# Flash_RAM.net
KiCad netlist of a schematic drawn in Altium Designer
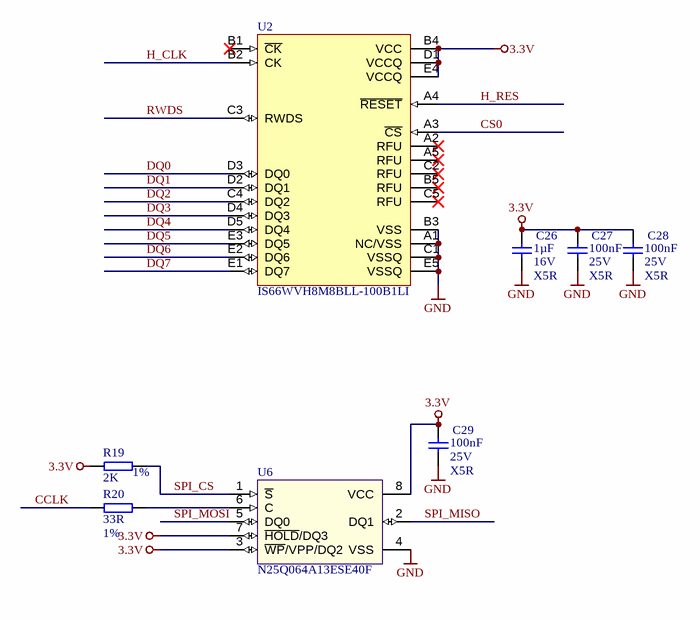
[diagram p0: Flash_RAM.SchDoc]

(export (version "E")
  (design (tool "Eeschema 10.0.6"))
  (components
    (comp (ref "C26")
      (value "1µF")
      (footprint "CAPC1005X55N")
      (description "KON 1µF 16V X5R 10% SMD BF 1005 (0402)")
      (fields
        (field (name "VOLTAGE") "16V")
        (field (name "TECHNOLOGY") "X5R")
        (field (name "TOLERANCE") "10%")
      )
      (libsource (lib "TE") (part "CAP-NP"))
    )
    (comp (ref "C27")
      (value "100nF")
      (footprint "CAPC1005X55N")
      (description "KON 100nF 25V X5R ±10% SMD BF 1005 (0402)")
      (fields (field (name "VOLTAGE") "25V") (field (name "TECHNOLOGY") "X5R"))
      (libsource (lib "TE") (part "CAP-NP"))
    )
    (comp (ref "C28")
      (value "100nF")
      (footprint "CAPC1005X55N")
      (description "KON 100nF 25V X5R ±10% SMD BF 1005 (0402)")
      (fields (field (name "VOLTAGE") "25V") (field (name "TECHNOLOGY") "X5R"))
      (libsource (lib "TE") (part "CAP-NP"))
    )
    (comp (ref "C29")
      (value "100nF")
      (footprint "CAPC1005X55N")
      (description "KON 100nF 25V X5R ±10% SMD BF 1005 (0402)")
      (fields (field (name "VOLTAGE") "25V") (field (name "TECHNOLOGY") "X5R"))
      (libsource (lib "TE") (part "CAP-NP"))
    )
    (comp (ref "R19")
      (value "2K")
      (footprint "RESC1005X40N")
      (description "WID SMD 2K 1% 0,063W")
      (fields (field (name "TOLERANCE") "1%"))
      (libsource (lib "TE") (part "RES"))
    )
    (comp (ref "R20")
      (value "33R")
      (footprint "RESC1005X40N")
      (description "WID SMD 33R 1% 0,063W BF 1005 (0402)")
      (fields (field (name "TOLERANCE") "1%"))
      (libsource (lib "TE") (part "RES"))
    )
    (comp (ref "U2")
      (value "IS66WVH8M8BLL-100B1LI")
      (footprint "BGA25C100P5X5_800X600X120N")
      (libsource (lib "TE") (part "IS6xWVH-B1"))
    )
    (comp (ref "U6")
      (value "N25Q064A13ESE40F")
      (footprint "SOIC127P790X191-8N")
      (description "N25Q064A13ESE40 64MBit Serial Flash")
      (libsource (lib "TE") (part "N25Q064-8Pin"))
    )
  )
  (nets
    (net (code "1") (name "/CCLK") (class "Default")
      (node (ref "R20") (pin "1") (pinfunction "1_1") (pintype "passive"))
    )
    (net (code "2") (name "/CS0") (class "Default")
      (node (ref "U2") (pin "A3") (pinfunction "~{CS}_A3") (pintype "input"))
    )
    (net (code "3") (name "/DQ0") (class "Default")
      (node (ref "U2") (pin "D3") (pinfunction "DQ0_D3") (pintype "bidirectional"))
    )
    (net (code "4") (name "/DQ1") (class "Default")
      (node (ref "U2") (pin "D2") (pinfunction "DQ1_D2") (pintype "bidirectional"))
    )
    (net (code "5") (name "/DQ2") (class "Default")
      (node (ref "U2") (pin "C4") (pinfunction "DQ2_C4") (pintype "bidirectional"))
    )
    (net (code "6") (name "/DQ3") (class "Default")
      (node (ref "U2") (pin "D4") (pinfunction "DQ3_D4") (pintype "bidirectional"))
    )
    (net (code "7") (name "/DQ4") (class "Default")
      (node (ref "U2") (pin "D5") (pinfunction "DQ4_D5") (pintype "bidirectional"))
    )
    (net (code "8") (name "/DQ5") (class "Default")
      (node (ref "U2") (pin "E3") (pinfunction "DQ5_E3") (pintype "bidirectional"))
    )
    (net (code "9") (name "/DQ6") (class "Default")
      (node (ref "U2") (pin "E2") (pinfunction "DQ6_E2") (pintype "bidirectional"))
    )
    (net (code "10") (name "/DQ7") (class "Default")
      (node (ref "U2") (pin "E1") (pinfunction "DQ7_E1") (pintype "bidirectional"))
    )
    (net (code "11") (name "/H_CLK") (class "Default")
      (node (ref "U2") (pin "B2") (pinfunction "CK_B2") (pintype "input"))
    )
    (net (code "12") (name "/H_RES") (class "Default")
      (node (ref "U2") (pin "A4") (pinfunction "~{RESET}_A4") (pintype "input"))
    )
    (net (code "13") (name "/RWDS") (class "Default")
      (node (ref "U2") (pin "C3") (pinfunction "RWDS_C3") (pintype "bidirectional"))
    )
    (net (code "14") (name "/SPI_CS") (class "Default")
      (node (ref "R19") (pin "2") (pinfunction "2_2") (pintype "passive"))
      (node (ref "U6") (pin "1") (pinfunction "~{S}_1") (pintype "input"))
    )
    (net (code "15") (name "/SPI_MISO") (class "Default")
      (node (ref "U6") (pin "2") (pinfunction "DQ1_2") (pintype "bidirectional"))
    )
    (net (code "16") (name "/SPI_MOSI") (class "Default")
      (node (ref "U6") (pin "5") (pinfunction "DQ0_5") (pintype "bidirectional"))
    )
    (net (code "17") (name "3.3V") (class "Default")
      (node (ref "C26") (pin "1") (pinfunction "1_1") (pintype "passive"))
      (node (ref "C27") (pin "1") (pinfunction "1_1") (pintype "passive"))
      (node (ref "C28") (pin "1") (pinfunction "1_1") (pintype "passive"))
      (node (ref "C29") (pin "1") (pinfunction "1_1") (pintype "passive"))
      (node (ref "R19") (pin "1") (pinfunction "1_1") (pintype "passive"))
      (node (ref "U2") (pin "B4") (pinfunction "VCC_B4") (pintype "power_in"))
      (node (ref "U2") (pin "D1") (pinfunction "VCCQ_D1") (pintype "power_in"))
      (node (ref "U2") (pin "E4") (pinfunction "VCCQ_E4") (pintype "power_in"))
      (node (ref "U6") (pin "3") (pinfunction "~{WP}/VPP/DQ2_3") (pintype "bidirectional"))
      (node (ref "U6") (pin "7") (pinfunction "~{HOLD}/DQ3_7") (pintype "bidirectional"))
      (node (ref "U6") (pin "8") (pinfunction "VCC_8") (pintype "power_in"))
    )
    (net (code "18") (name "GND") (class "Default")
      (node (ref "C26") (pin "2") (pinfunction "2_2") (pintype "passive"))
      (node (ref "C27") (pin "2") (pinfunction "2_2") (pintype "passive"))
      (node (ref "C28") (pin "2") (pinfunction "2_2") (pintype "passive"))
      (node (ref "C29") (pin "2") (pinfunction "2_2") (pintype "passive"))
      (node (ref "U2") (pin "A1") (pinfunction "NC/VSS_A1") (pintype "power_in"))
      (node (ref "U2") (pin "B3") (pinfunction "VSS_B3") (pintype "power_in"))
      (node (ref "U2") (pin "C1") (pinfunction "VSSQ_C1") (pintype "power_in"))
      (node (ref "U2") (pin "E5") (pinfunction "VSSQ_E5") (pintype "power_in"))
      (node (ref "U6") (pin "4") (pinfunction "VSS_4") (pintype "power_in"))
    )
    (net (code "19") (name "Net-(U6-C)") (class "Default")
      (node (ref "R20") (pin "2") (pinfunction "2_2") (pintype "passive"))
      (node (ref "U6") (pin "6") (pinfunction "C_6") (pintype "input"))
    )
    (net (code "20") (name "unconnected-(U2-RFU-PadA2)") (class "Default")
      (node (ref "U2") (pin "A2") (pinfunction "RFU_A2") (pintype "passive+no_connect"))
    )
    (net (code "21") (name "unconnected-(U2-RFU-PadA5)") (class "Default")
      (node (ref "U2") (pin "A5") (pinfunction "RFU_A5") (pintype "passive+no_connect"))
    )
    (net (code "22") (name "unconnected-(U2-RFU-PadB5)") (class "Default")
      (node (ref "U2") (pin "B5") (pinfunction "RFU_B5") (pintype "passive+no_connect"))
    )
    (net (code "23") (name "unconnected-(U2-RFU-PadC2)") (class "Default")
      (node (ref "U2") (pin "C2") (pinfunction "RFU_C2") (pintype "passive+no_connect"))
    )
    (net (code "24") (name "unconnected-(U2-RFU-PadC5)") (class "Default")
      (node (ref "U2") (pin "C5") (pinfunction "RFU_C5") (pintype "passive+no_connect"))
    )
    (net (code "25") (name "unconnected-(U2-~{CK}-PadB1)") (class "Default")
      (node (ref "U2") (pin "B1") (pinfunction "~{CK}_B1") (pintype "input+no_connect"))
    )
  )
)
